# Sheet1.net
KiCad netlist of a schematic drawn in Altium Designer
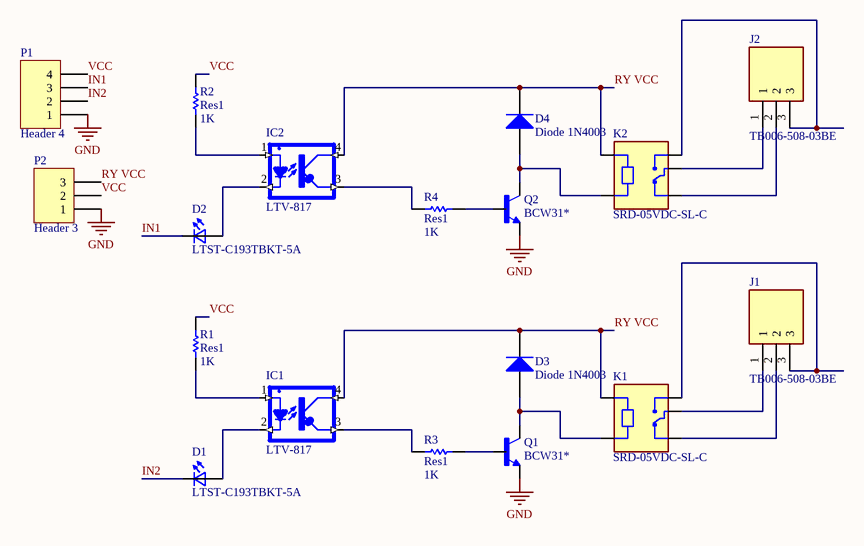
[diagram p0: Sheet1.SchDoc]

(export (version "E")
  (design (tool "Eeschema 10.0.6"))
  (components
    (comp (ref "D1")
      (value "LTST-C193TBKT-5A")
      (footprint "0603")
      (description "Blue 470nm LED Indication - Discrete 2.8V 0603 _1608 Metric_")
      (fields (field (name "DIGI-KEY_PART_NUMBER") "160-1827-1-ND") (field (name "MF") "Lite-On Inc."))
      (libsource (lib "SnapEDAsch") (part "LTST-C193TBKT-5A"))
    )
    (comp (ref "D2")
      (value "LTST-C193TBKT-5A")
      (footprint "0603")
      (description "Blue 470nm LED Indication - Discrete 2.8V 0603 _1608 Metric_")
      (fields (field (name "DIGI-KEY_PART_NUMBER") "160-1827-1-ND") (field (name "MF") "Lite-On Inc."))
      (libsource (lib "SnapEDAsch") (part "LTST-C193TBKT-5A"))
    )
    (comp (ref "D3")
      (value "Diode 1N4003")
      (footprint "DO-41")
      (description "1 Amp General Purpose Rectifier")
      (fields (field (name "PUBLISHER") "Altium Limited"))
      (libsource (lib "Miscellaneous Devices") (part "Diode 1N4003"))
    )
    (comp (ref "D4")
      (value "Diode 1N4003")
      (footprint "DO-41")
      (description "1 Amp General Purpose Rectifier")
      (fields (field (name "PUBLISHER") "Altium Limited"))
      (libsource (lib "Miscellaneous Devices") (part "Diode 1N4003"))
    )
    (comp (ref "IC1")
      (value "LTV-817")
      (footprint "DIP-4")
      (description "Optoisolator Transistor Output 5000Vrms 1 Channel 4-SMD")
      (fields (field (name "MF") "Lite-On Electronics"))
      (libsource (lib "SnapEDAsch") (part "LTV-817"))
    )
    (comp (ref "IC2")
      (value "LTV-817")
      (footprint "DIP-4")
      (description "Optoisolator Transistor Output 5000Vrms 1 Channel 4-SMD")
      (fields (field (name "MF") "Lite-On Electronics"))
      (libsource (lib "SnapEDAsch") (part "LTV-817"))
    )
    (comp (ref "J1")
      (value "TB006-508-03BE")
      (footprint "CUI_TB006-508-03BE")
      (description "2~24 Poles, Screw Type, Horizontal, 5.08 Pitch, 26~14 (AWG), Terminal Block Connector")
      (fields (field (name "MF") "CUI Devices"))
      (libsource (lib "TB006-508-03BE") (part "TB006-508-03BE"))
    )
    (comp (ref "J2")
      (value "TB006-508-03BE")
      (footprint "CUI_TB006-508-03BE")
      (description "2~24 Poles, Screw Type, Horizontal, 5.08 Pitch, 26~14 (AWG), Terminal Block Connector")
      (fields (field (name "MF") "CUI Devices"))
      (libsource (lib "TB006-508-03BE") (part "TB006-508-03BE"))
    )
    (comp (ref "K1")
      (value "SRD-05VDC-SL-C")
      (footprint "RELAY_SRD-05VDC-SL-C")
      (fields (field (name "MF") "Songle Relay"))
      (libsource (lib "SRD-05VDC-SL-C") (part "SRD-05VDC-SL-C"))
    )
    (comp (ref "K2")
      (value "SRD-05VDC-SL-C")
      (footprint "RELAY_SRD-05VDC-SL-C")
      (fields (field (name "MF") "Songle Relay"))
      (libsource (lib "SRD-05VDC-SL-C") (part "SRD-05VDC-SL-C"))
    )
    (comp (ref "P1")
      (value "Header 4")
      (footprint "HDR1X4")
      (description "Header, 4-Pin")
      (fields (field (name "PUBLISHER") "Altium Limited"))
      (libsource (lib "Miscellaneous Connectors") (part "Header 4"))
    )
    (comp (ref "P2")
      (value "Header 3")
      (footprint "HDR1X3")
      (description "Header, 3-Pin")
      (fields (field (name "PUBLISHER") "Altium Limited"))
      (libsource (lib "Miscellaneous Connectors") (part "Header 3"))
    )
    (comp (ref "Q1")
      (value "BCW31*")
      (footprint "SOT23-BEC")
      (description "Bipolar _BJT_ Transistor NPN General Purpose Amplifier Surface Mount")
      (fields (field (name "MF") "ON Semiconductor") (field (name "MP") "BCW31"))
      (libsource (lib "SnapEDAsch") (part "BCW31*"))
    )
    (comp (ref "Q2")
      (value "BCW31*")
      (footprint "SOT23-BEC")
      (description "Bipolar _BJT_ Transistor NPN General Purpose Amplifier Surface Mount")
      (fields (field (name "MF") "ON Semiconductor") (field (name "MP") "BCW31"))
      (libsource (lib "SnapEDAsch") (part "BCW31*"))
    )
    (comp (ref "R1")
      (value "Res1")
      (footprint "AXIAL-0.3")
      (description "Resistor")
      (fields (field (name "ALTIUM_VALUE") "1K") (field (name "PUBLISHER") "Altium Limited"))
      (libsource (lib "Miscellaneous Devices") (part "Res1"))
    )
    (comp (ref "R2")
      (value "Res1")
      (footprint "AXIAL-0.3")
      (description "Resistor")
      (fields (field (name "ALTIUM_VALUE") "1K") (field (name "PUBLISHER") "Altium Limited"))
      (libsource (lib "Miscellaneous Devices") (part "Res1"))
    )
    (comp (ref "R3")
      (value "Res1")
      (footprint "AXIAL-0.3")
      (description "Resistor")
      (fields (field (name "ALTIUM_VALUE") "1K") (field (name "PUBLISHER") "Altium Limited"))
      (libsource (lib "Miscellaneous Devices") (part "Res1"))
    )
    (comp (ref "R4")
      (value "Res1")
      (footprint "AXIAL-0.3")
      (description "Resistor")
      (fields (field (name "ALTIUM_VALUE") "1K") (field (name "PUBLISHER") "Altium Limited"))
      (libsource (lib "Miscellaneous Devices") (part "Res1"))
    )
  )
  (nets
    (net (code "1") (name "/IN1") (class "Default")
      (node (ref "D2") (pin "1") (pinfunction "K2_1") (pintype "passive"))
      (node (ref "P1") (pin "3") (pinfunction "3_3") (pintype "passive"))
    )
    (net (code "2") (name "/IN2") (class "Default")
      (node (ref "D1") (pin "1") (pinfunction "K2_1") (pintype "passive"))
      (node (ref "P1") (pin "2") (pinfunction "2_2") (pintype "passive"))
    )
    (net (code "3") (name "/RY VCC") (class "Default")
      (node (ref "D3") (pin "2") (pinfunction "K_2") (pintype "passive"))
      (node (ref "D4") (pin "2") (pinfunction "K_2") (pintype "passive"))
      (node (ref "IC1") (pin "4") (pinfunction "4_4") (pintype "input"))
      (node (ref "IC2") (pin "4") (pinfunction "4_4") (pintype "input"))
      (node (ref "K1") (pin "A1") (pinfunction "A1_A1") (pintype "passive"))
      (node (ref "K2") (pin "A1") (pinfunction "A1_A1") (pintype "passive"))
      (node (ref "P2") (pin "3") (pinfunction "3_3") (pintype "passive"))
    )
    (net (code "4") (name "/VCC") (class "Default")
      (node (ref "P1") (pin "4") (pinfunction "4_4") (pintype "passive"))
      (node (ref "P2") (pin "2") (pinfunction "2_2") (pintype "passive"))
      (node (ref "R1") (pin "2") (pinfunction "2_2") (pintype "passive"))
      (node (ref "R2") (pin "2") (pinfunction "2_2") (pintype "passive"))
    )
    (net (code "5") (name "GND") (class "Default")
      (node (ref "P1") (pin "1") (pinfunction "1_1") (pintype "passive"))
      (node (ref "P2") (pin "1") (pinfunction "1_1") (pintype "passive"))
      (node (ref "Q1") (pin "E") (pinfunction "E_E") (pintype "passive"))
      (node (ref "Q2") (pin "E") (pinfunction "E_E") (pintype "passive"))
    )
    (net (code "6") (name "Net-(D1-A2)") (class "Default")
      (node (ref "D1") (pin "2") (pinfunction "A2_2") (pintype "passive"))
      (node (ref "IC1") (pin "2") (pinfunction "2_2") (pintype "output"))
    )
    (net (code "7") (name "Net-(D2-A2)") (class "Default")
      (node (ref "D2") (pin "2") (pinfunction "A2_2") (pintype "passive"))
      (node (ref "IC2") (pin "2") (pinfunction "2_2") (pintype "output"))
    )
    (net (code "8") (name "Net-(D3-A)") (class "Default")
      (node (ref "D3") (pin "1") (pinfunction "A_1") (pintype "passive"))
      (node (ref "K1") (pin "A2") (pinfunction "A2_A2") (pintype "passive"))
      (node (ref "Q1") (pin "C") (pinfunction "C_C") (pintype "passive"))
    )
    (net (code "9") (name "Net-(D4-A)") (class "Default")
      (node (ref "D4") (pin "1") (pinfunction "A_1") (pintype "passive"))
      (node (ref "K2") (pin "A2") (pinfunction "A2_A2") (pintype "passive"))
      (node (ref "Q2") (pin "C") (pinfunction "C_C") (pintype "passive"))
    )
    (net (code "10") (name "Net-(IC1-Pad1)") (class "Default")
      (node (ref "IC1") (pin "1") (pinfunction "1_1") (pintype "input"))
      (node (ref "R1") (pin "1") (pinfunction "1_1") (pintype "passive"))
    )
    (net (code "11") (name "Net-(IC1-Pad3)") (class "Default")
      (node (ref "IC1") (pin "3") (pinfunction "3_3") (pintype "output"))
      (node (ref "R3") (pin "1") (pinfunction "1_1") (pintype "passive"))
    )
    (net (code "12") (name "Net-(IC2-Pad1)") (class "Default")
      (node (ref "IC2") (pin "1") (pinfunction "1_1") (pintype "input"))
      (node (ref "R2") (pin "1") (pinfunction "1_1") (pintype "passive"))
    )
    (net (code "13") (name "Net-(IC2-Pad3)") (class "Default")
      (node (ref "IC2") (pin "3") (pinfunction "3_3") (pintype "output"))
      (node (ref "R4") (pin "1") (pinfunction "1_1") (pintype "passive"))
    )
    (net (code "14") (name "Net-(J1-Pad1)") (class "Default")
      (node (ref "J1") (pin "1") (pinfunction "1_1") (pintype "passive"))
      (node (ref "K1") (pin "COM") (pinfunction "COM_COM") (pintype "passive"))
    )
    (net (code "15") (name "Net-(J1-Pad2)") (class "Default")
      (node (ref "J1") (pin "2") (pinfunction "2_2") (pintype "passive"))
      (node (ref "K1") (pin "NC") (pinfunction "NC_NC") (pintype "passive"))
    )
    (net (code "16") (name "Net-(J1-Pad3)") (class "Default")
      (node (ref "J1") (pin "3") (pinfunction "3_3") (pintype "passive"))
      (node (ref "K1") (pin "NO") (pinfunction "NO_NO") (pintype "passive"))
    )
    (net (code "17") (name "Net-(J2-Pad1)") (class "Default")
      (node (ref "J2") (pin "1") (pinfunction "1_1") (pintype "passive"))
      (node (ref "K2") (pin "COM") (pinfunction "COM_COM") (pintype "passive"))
    )
    (net (code "18") (name "Net-(J2-Pad2)") (class "Default")
      (node (ref "J2") (pin "2") (pinfunction "2_2") (pintype "passive"))
      (node (ref "K2") (pin "NC") (pinfunction "NC_NC") (pintype "passive"))
    )
    (net (code "19") (name "Net-(J2-Pad3)") (class "Default")
      (node (ref "J2") (pin "3") (pinfunction "3_3") (pintype "passive"))
      (node (ref "K2") (pin "NO") (pinfunction "NO_NO") (pintype "passive"))
    )
    (net (code "20") (name "Net-(Q1-PadB)") (class "Default")
      (node (ref "Q1") (pin "B") (pinfunction "B_B") (pintype "passive"))
      (node (ref "R3") (pin "2") (pinfunction "2_2") (pintype "passive"))
    )
    (net (code "21") (name "Net-(Q2-PadB)") (class "Default")
      (node (ref "Q2") (pin "B") (pinfunction "B_B") (pintype "passive"))
      (node (ref "R4") (pin "2") (pinfunction "2_2") (pintype "passive"))
    )
  )
)
